# design.net
KiCad netlist of a schematic drawn in EasyEDA
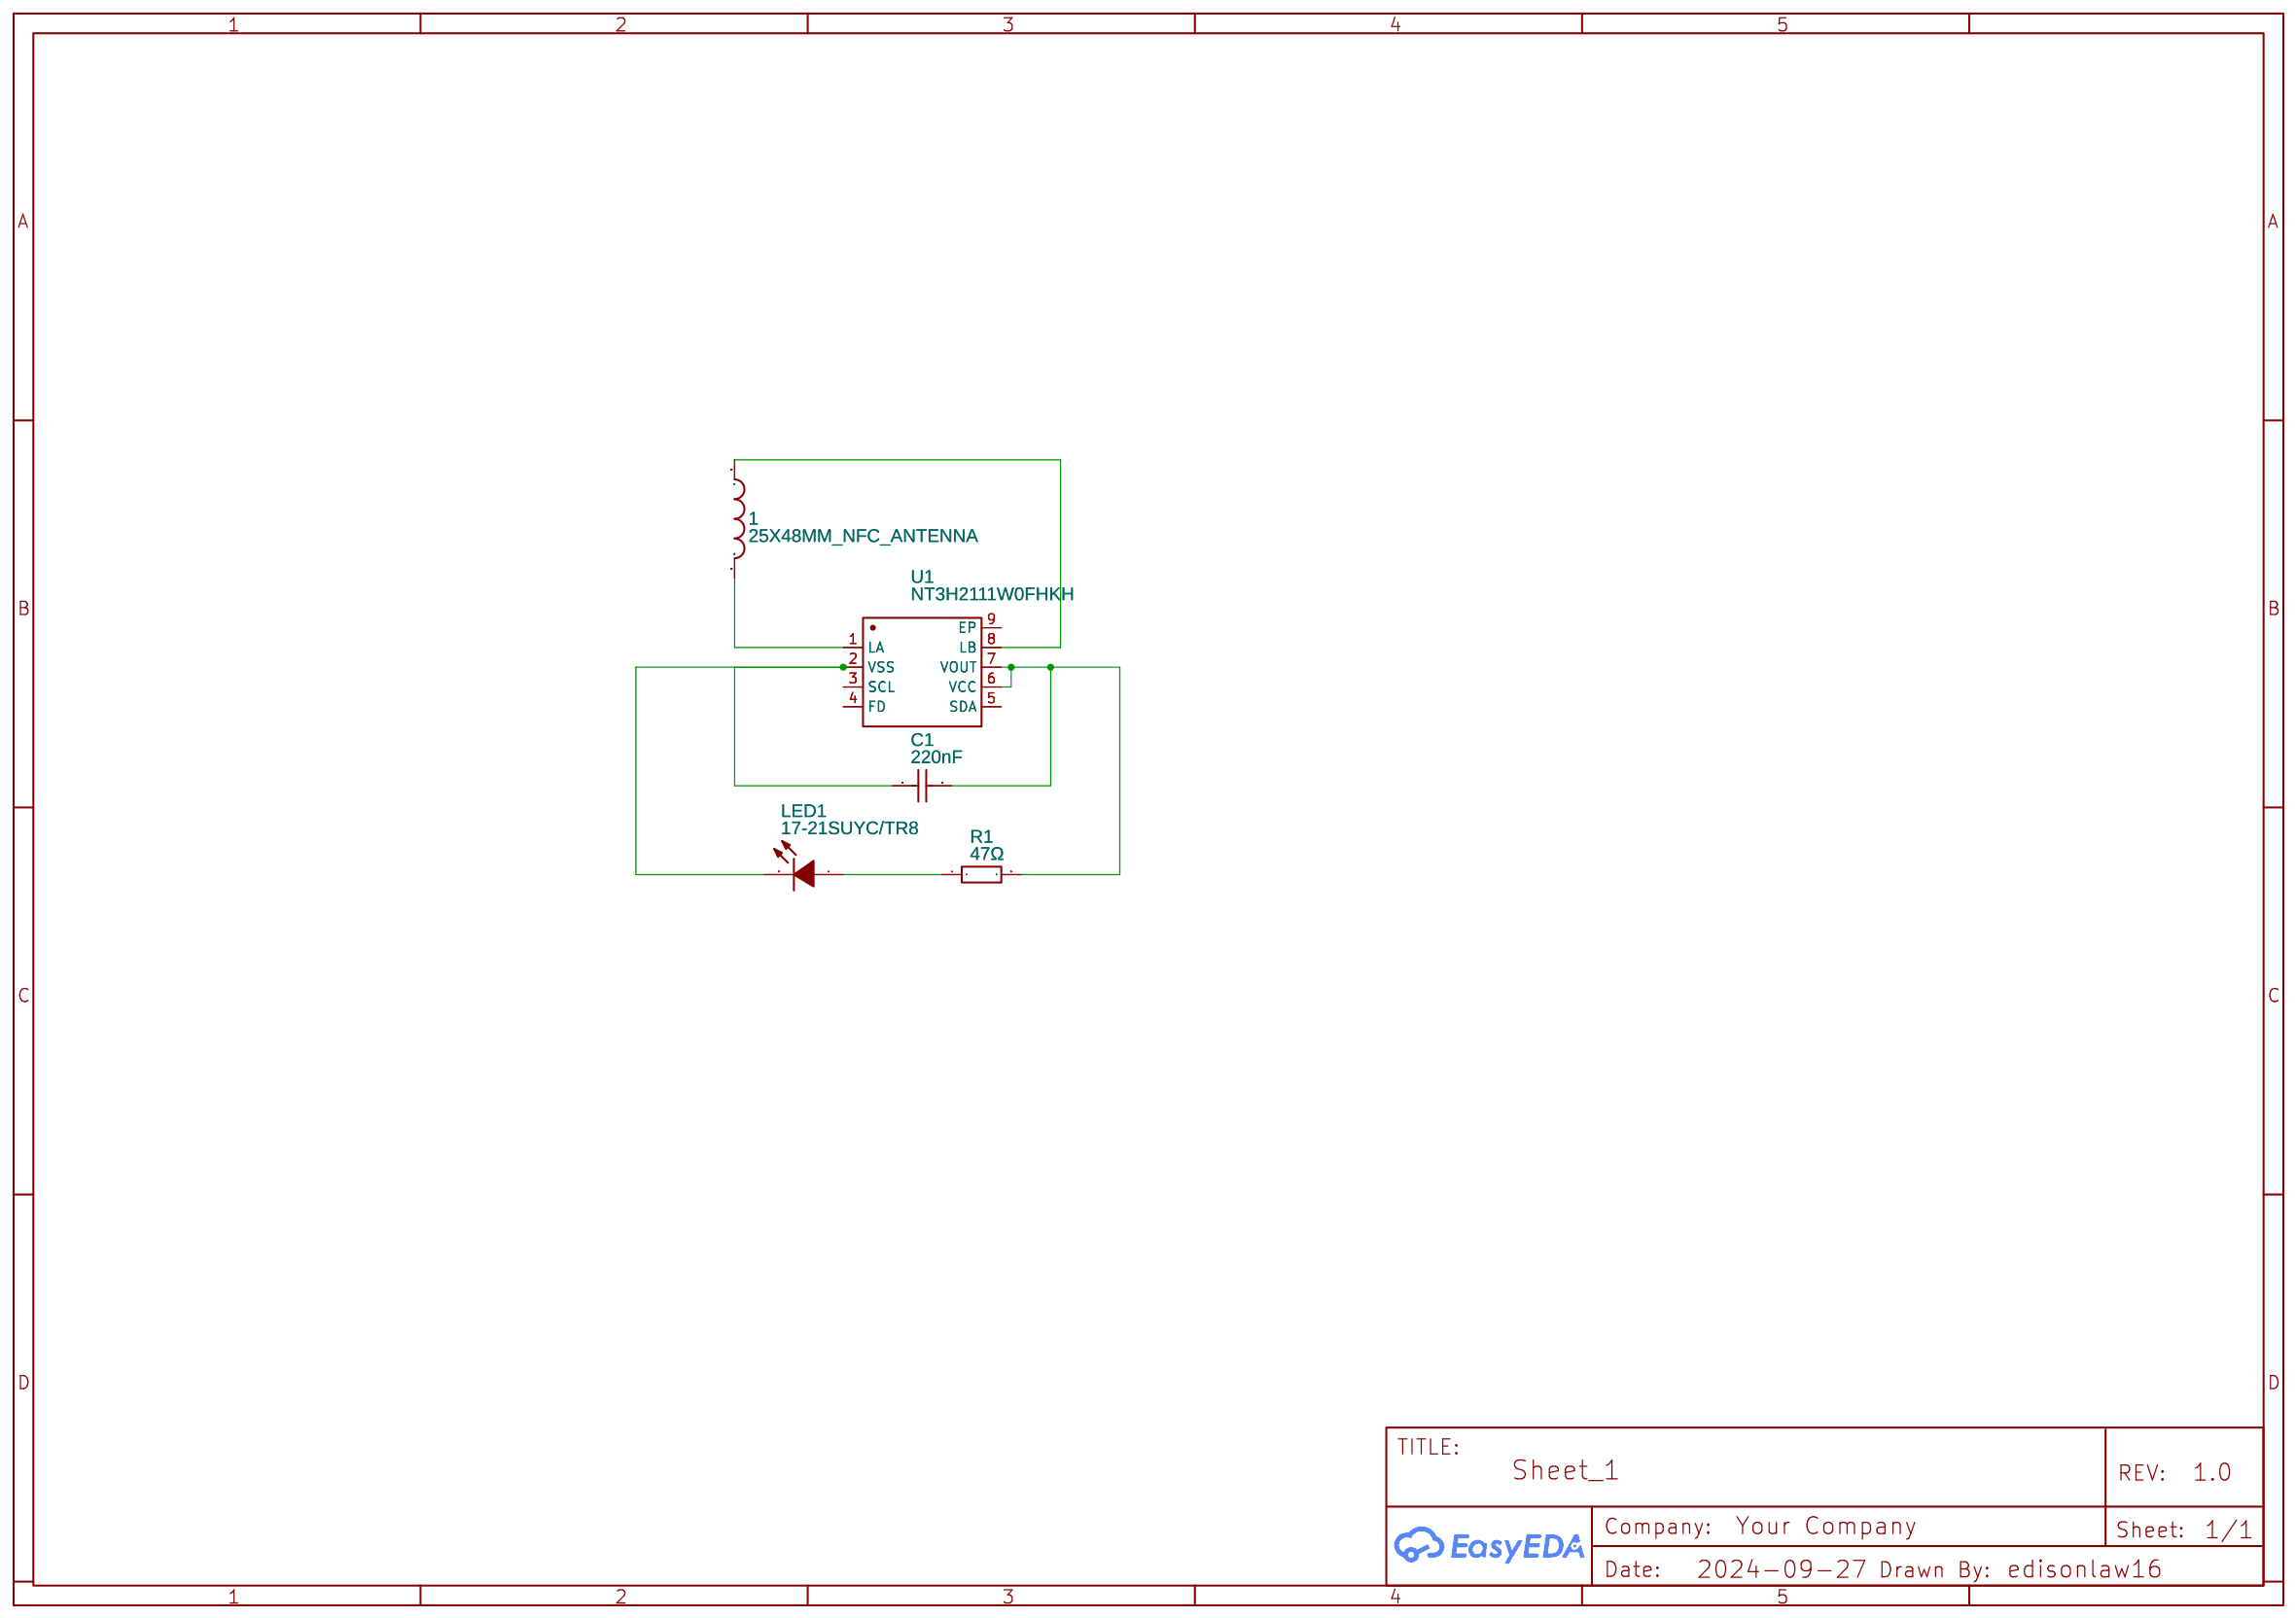
[diagram p0: schematic sheet]

(export (version "E")
  (design (tool "Eeschema 10.0.6"))
  (components
    (comp (ref "1") (value "25X48MM_NFC_ANTENNA") (libsource (lib "") (part "25X48MM_NFC_ANTENNA")))
    (comp (ref "C1")
      (value "220nF")
      (fields
        (field (name "Manufacturer Part") "CL10B224KA8NNNC")
        (field (name "Manufacturer") "SAMSUNG(三星)")
      )
      (libsource (lib "") (part "CL10B224KA8NNNC"))
    )
    (comp (ref "LED1")
      (value "17-21SUYC/TR8")
      (fields (field (name "Manufacturer Part") "KT-0805黄灯") (field (name "Manufacturer") "KENTO"))
      (libsource (lib "") (part "17-21SUYC/TR8"))
    )
    (comp (ref "R1")
      (value "47Ω")
      (fields
        (field (name "Manufacturer Part") "0603WAF470JT5E")
        (field (name "Manufacturer") "UNI-ROYAL(厚声)")
      )
      (libsource (lib "") (part "0603WAF470JT5E"))
    )
    (comp (ref "U1")
      (value "NT3H2111W0FHKH")
      (fields (field (name "Manufacturer") "NXP(恩智浦)"))
      (libsource (lib "") (part "NT3H2111W0FHKH"))
    )
  )
  (nets
    (net (code "1") (name "Net-(LED1-+)") (class "Default")
      (node (ref "LED1") (pin "1") (pinfunction "+_1") (pintype "unspecified"))
      (node (ref "R1") (pin "1") (pinfunction "1_1") (pintype "input"))
    )
    (net (code "2") (name "Net-(LED1--)") (class "Default")
      (node (ref "C1") (pin "1") (pinfunction "1_1") (pintype "input"))
      (node (ref "LED1") (pin "2") (pinfunction "-_2") (pintype "unspecified"))
      (node (ref "U1") (pin "2") (pinfunction "VSS_2") (pintype "unspecified"))
    )
    (net (code "3") (name "Net-(U1-LA)") (class "Default")
      (node (ref "1") (pin "P$2") (pinfunction "P$2_P$2") (pintype "bidirectional"))
      (node (ref "U1") (pin "1") (pinfunction "LA_1") (pintype "unspecified"))
    )
    (net (code "4") (name "Net-(U1-LB)") (class "Default")
      (node (ref "1") (pin "P$1") (pinfunction "P$1_P$1") (pintype "bidirectional"))
      (node (ref "U1") (pin "8") (pinfunction "LB_8") (pintype "unspecified"))
    )
    (net (code "5") (name "Net-(U1-VCC)") (class "Default")
      (node (ref "C1") (pin "2") (pinfunction "2_2") (pintype "input"))
      (node (ref "R1") (pin "2") (pinfunction "2_2") (pintype "input"))
      (node (ref "U1") (pin "6") (pinfunction "VCC_6") (pintype "unspecified"))
      (node (ref "U1") (pin "7") (pinfunction "VOUT_7") (pintype "unspecified"))
    )
    (net (code "6") (name "unconnected-(U1-EP-Pad9)") (class "Default")
      (node (ref "U1") (pin "9") (pinfunction "EP_9") (pintype "unspecified"))
    )
    (net (code "7") (name "unconnected-(U1-FD-Pad4)") (class "Default")
      (node (ref "U1") (pin "4") (pinfunction "FD_4") (pintype "unspecified"))
    )
    (net (code "8") (name "unconnected-(U1-SCL-Pad3)") (class "Default")
      (node (ref "U1") (pin "3") (pinfunction "SCL_3") (pintype "unspecified"))
    )
    (net (code "9") (name "unconnected-(U1-SDA-Pad5)") (class "Default")
      (node (ref "U1") (pin "5") (pinfunction "SDA_5") (pintype "unspecified"))
    )
  )
)
